# AIO-RF-v2-Sheet2.net
KiCad netlist of a schematic drawn in Altium Designer
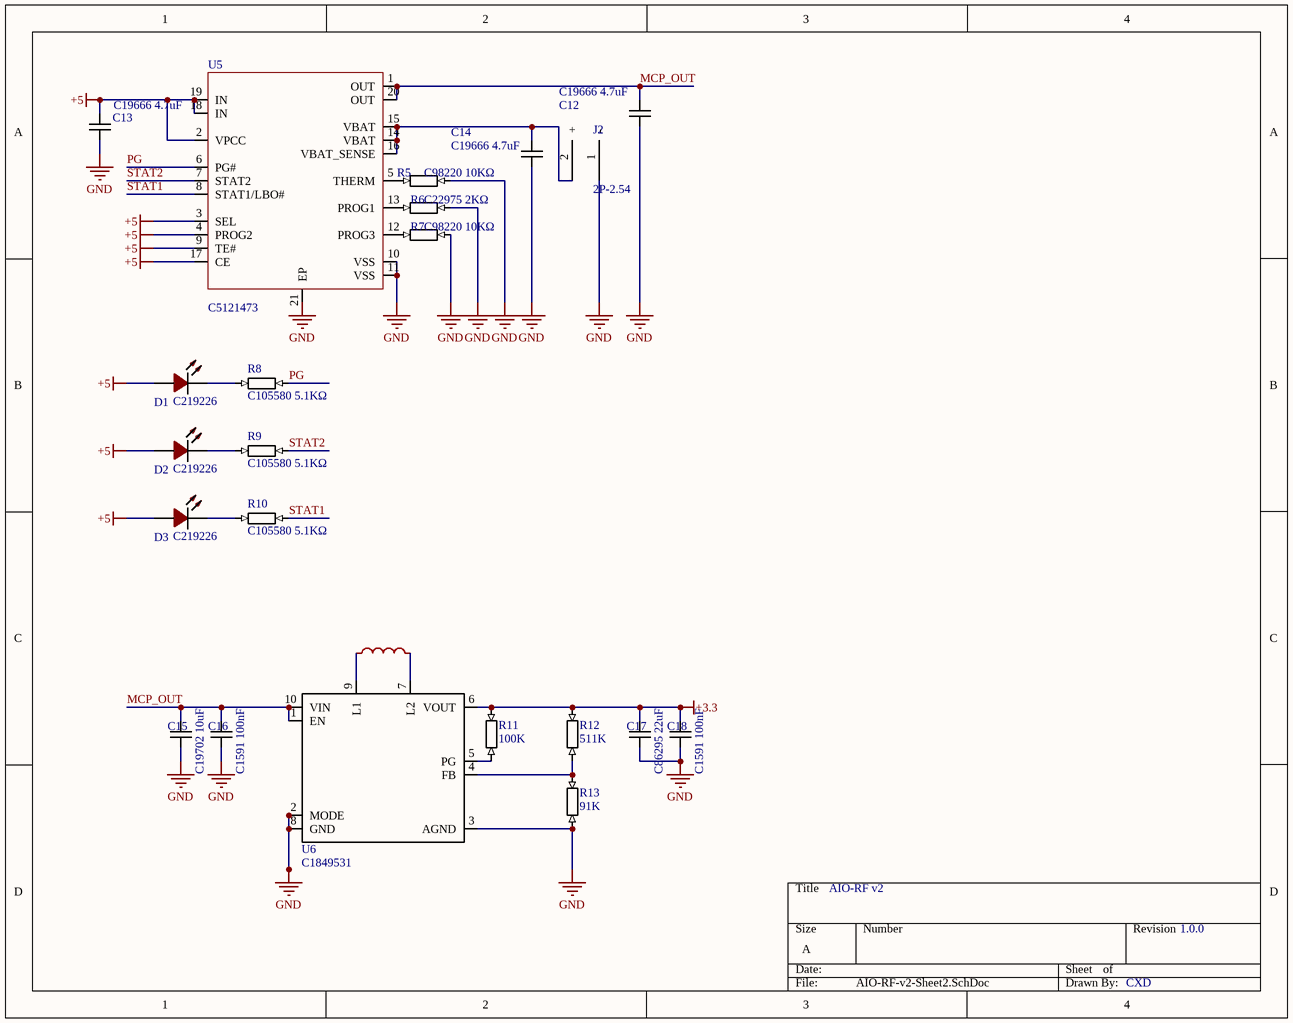
[diagram p0: AIO-RF-v2-Sheet2.SchDoc]

(export (version "E")
  (design (tool "Eeschema 10.0.6"))
  (components
    (comp (ref "C12")
      (value "C19666 4.7uF")
      (footprint "C19666")
      (description "4.7uF (475) ±10% 16V")
      (fields
        (field (name "LCSC PART NUMBER") "C19666")
        (field (name "MANUFACTURER") "SAMSUNG(三星)")
        (field (name "IMPORTED BY") "JLCAltiumImporter 0.3.1")
      )
      (libsource (lib "Schlib1") (part "C19666"))
    )
    (comp (ref "C13")
      (value "C19666 4.7uF")
      (footprint "C19666")
      (description "4.7uF (475) ±10% 16V")
      (fields
        (field (name "LCSC PART NUMBER") "C19666")
        (field (name "MANUFACTURER") "SAMSUNG(三星)")
        (field (name "IMPORTED BY") "JLCAltiumImporter 0.3.1")
      )
      (libsource (lib "Schlib1") (part "C19666"))
    )
    (comp (ref "C14")
      (value "C19666 4.7uF")
      (footprint "C19666")
      (description "4.7uF (475) ±10% 16V")
      (fields
        (field (name "LCSC PART NUMBER") "C19666")
        (field (name "MANUFACTURER") "SAMSUNG(三星)")
        (field (name "IMPORTED BY") "JLCAltiumImporter 0.3.1")
      )
      (libsource (lib "Schlib1") (part "C19666"))
    )
    (comp (ref "C15")
      (value "C19702 10uF")
      (footprint "C19702")
      (fields
        (field (name "LCSC PART NUMBER") "C19702")
        (field (name "MANUFACTURER") "SAMSUNG(三星)")
        (field (name "MANUFACTURER PART NUMBER") "CL10A106KP8NNNC")
        (field (name "IMPORTED BY") "JLCAltiumImporter 0.3.1")
      )
      (libsource (lib "Schlib1") (part "C19702"))
    )
    (comp (ref "C16")
      (value "C1591 100nF")
      (footprint "C1591")
      (description "100nF (104) ±10% 50V")
      (fields
        (field (name "LCSC PART NUMBER") "C1591")
        (field (name "MANUFACTURER") "SAMSUNG(三星)")
        (field (name "IMPORTED BY") "JLCAltiumImporter 0.3.1")
      )
      (libsource (lib "Schlib1") (part "C1591"))
    )
    (comp (ref "C17")
      (value "C86295 22uF")
      (footprint "C86295")
      (fields
        (field (name "LCSC PART NUMBER") "C86295")
        (field (name "MANUFACTURER") "SAMSUNG(三星)")
        (field (name "MANUFACTURER PART NUMBER") "CL10A226MP8NUNE")
        (field (name "IMPORTED BY") "JLCAltiumImporter 0.3.1")
      )
      (libsource (lib "Schlib1") (part "C86295"))
    )
    (comp (ref "C18")
      (value "C1591 100nF")
      (footprint "C1591")
      (description "100nF (104) ±10% 50V")
      (fields
        (field (name "LCSC PART NUMBER") "C1591")
        (field (name "MANUFACTURER") "SAMSUNG(三星)")
        (field (name "IMPORTED BY") "JLCAltiumImporter 0.3.1")
      )
      (libsource (lib "Schlib1") (part "C1591"))
    )
    (comp (ref "D1")
      (value "C219226")
      (footprint "C219226")
      (fields
        (field (name "MANUFACTURER") "HONGLITRONIC(鸿利光电)")
        (field (name "MANUFACTURER PART NUMBER") "HL-PST-1608H233W(9000-16000K)")
        (field (name "IMPORTED BY") "JLCAltiumImporter 0.3.2")
      )
      (libsource (lib "Schlib1") (part "C219226"))
    )
    (comp (ref "D2")
      (value "C219226")
      (footprint "C219226")
      (fields
        (field (name "MANUFACTURER") "HONGLITRONIC(鸿利光电)")
        (field (name "MANUFACTURER PART NUMBER") "HL-PST-1608H233W(9000-16000K)")
        (field (name "IMPORTED BY") "JLCAltiumImporter 0.3.2")
      )
      (libsource (lib "Schlib1") (part "C219226"))
    )
    (comp (ref "D3")
      (value "C219226")
      (footprint "C219226")
      (fields
        (field (name "MANUFACTURER") "HONGLITRONIC(鸿利光电)")
        (field (name "MANUFACTURER PART NUMBER") "HL-PST-1608H233W(9000-16000K)")
        (field (name "IMPORTED BY") "JLCAltiumImporter 0.3.2")
      )
      (libsource (lib "Schlib1") (part "C219226"))
    )
    (comp (ref "J2")
      (value "2P-2.54")
      (footprint "PcbLib1:2P-2.54")
      (libsource (lib "Schlib1") (part "2P-2.54"))
    )
    (comp (ref "L1")
      (value "hctc-201610-1r0-m")
      (footprint "PcbLib1:Inductor")
      (fields
        (field (name "MANUFACTURER") "YOUCHI(佑驰)")
        (field (name "MANUFACTURERPART") "HCTC-201610-1R0-M")
      )
      (libsource (lib "altium-import") (part "root_0_hctc-201610-1r0-m_"))
    )
    (comp (ref "R5")
      (value "C98220 10KΩ")
      (footprint "C98220")
      (fields
        (field (name "LCSC PART NUMBER") "C98220")
        (field (name "MANUFACTURER") "YAGEO(国巨)")
        (field (name "MANUFACTURER PART NUMBER") "RC0603FR-0710KL")
        (field (name "IMPORTED BY") "JLCAltiumImporter 0.3.1")
      )
      (libsource (lib "Schlib1") (part "C98220"))
    )
    (comp (ref "R6")
      (value "C22975 2KΩ")
      (footprint "C22975")
      (description "2KΩ (2001) ±1%")
      (fields
        (field (name "LCSC PART NUMBER") "C22975")
        (field (name "MANUFACTURER") "UNI-ROYAL(厚声)")
        (field (name "IMPORTED BY") "JLCAltiumImporter 0.3.1")
      )
      (libsource (lib "Schlib1") (part "C22975"))
    )
    (comp (ref "R7")
      (value "C98220 10KΩ")
      (footprint "C98220")
      (fields
        (field (name "LCSC PART NUMBER") "C98220")
        (field (name "MANUFACTURER") "YAGEO(国巨)")
        (field (name "MANUFACTURER PART NUMBER") "RC0603FR-0710KL")
        (field (name "IMPORTED BY") "JLCAltiumImporter 0.3.1")
      )
      (libsource (lib "Schlib1") (part "C98220"))
    )
    (comp (ref "R8")
      (value "C105580 5.1KΩ")
      (footprint "C105580")
      (fields
        (field (name "MANUFACTURER") "YAGEO(国巨)")
        (field (name "MANUFACTURER PART NUMBER") "RC0603FR-075K1L")
        (field (name "LCSC PART NUMBER") "C105580")
        (field (name "IMPORTED BY") "JLCAltiumImporter 0.3.1")
      )
      (libsource (lib "Schlib1") (part "C105580"))
    )
    (comp (ref "R9")
      (value "C105580 5.1KΩ")
      (footprint "C105580")
      (fields
        (field (name "MANUFACTURER") "YAGEO(国巨)")
        (field (name "MANUFACTURER PART NUMBER") "RC0603FR-075K1L")
        (field (name "LCSC PART NUMBER") "C105580")
        (field (name "IMPORTED BY") "JLCAltiumImporter 0.3.1")
      )
      (libsource (lib "Schlib1") (part "C105580"))
    )
    (comp (ref "R10")
      (value "C105580 5.1KΩ")
      (footprint "C105580")
      (fields
        (field (name "MANUFACTURER") "YAGEO(国巨)")
        (field (name "MANUFACTURER PART NUMBER") "RC0603FR-075K1L")
        (field (name "LCSC PART NUMBER") "C105580")
        (field (name "IMPORTED BY") "JLCAltiumImporter 0.3.1")
      )
      (libsource (lib "Schlib1") (part "C105580"))
    )
    (comp (ref "R11")
      (value "100K")
      (footprint "C22975")
      (description "2KΩ (2001) ±1%")
      (fields
        (field (name "LCSC PART NUMBER") "C22975")
        (field (name "MANUFACTURER") "UNI-ROYAL(厚声)")
        (field (name "IMPORTED BY") "JLCAltiumImporter 0.3.1")
      )
      (libsource (lib "Schlib1") (part "C22975"))
    )
    (comp (ref "R12")
      (value "511K")
      (footprint "C22975")
      (description "2KΩ (2001) ±1%")
      (fields
        (field (name "LCSC PART NUMBER") "C22975")
        (field (name "MANUFACTURER") "UNI-ROYAL(厚声)")
        (field (name "IMPORTED BY") "JLCAltiumImporter 0.3.1")
      )
      (libsource (lib "Schlib1") (part "C22975"))
    )
    (comp (ref "R13")
      (value "91K")
      (footprint "C22975")
      (description "2KΩ (2001) ±1%")
      (fields
        (field (name "LCSC PART NUMBER") "C22975")
        (field (name "MANUFACTURER") "UNI-ROYAL(厚声)")
        (field (name "IMPORTED BY") "JLCAltiumImporter 0.3.1")
      )
      (libsource (lib "Schlib1") (part "C22975"))
    )
    (comp (ref "U5")
      (value "C5121473")
      (footprint "C5121473")
      (fields
        (field (name "MANUFACTURER") "MICROCHIP(美国微芯)")
        (field (name "MANUFACTURER PART NUMBER") "MCP73871-2CCI/ML")
        (field (name "IMPORTED BY") "JLCAltiumImporter 0.3.1")
      )
      (libsource (lib "Schlib1") (part "C5121473"))
    )
    (comp (ref "U6")
      (value "C1849531")
      (footprint "C1849531")
      (fields
        (field (name "MANUFACTURER") "TI(德州仪器)")
        (field (name "MANUFACTURER PART NUMBER") "TPS63802DLAT")
        (field (name "IMPORTED BY") "JLCAltiumImporter 0.3.5")
      )
      (libsource (lib "Schlib1") (part "C1849531"))
    )
  )
  (nets
    (net (code "1") (name "+3.3") (class "Default")
      (node (ref "C17") (pin "2") (pinfunction "2_2") (pintype "passive"))
      (node (ref "C18") (pin "2") (pinfunction "2_2") (pintype "passive"))
      (node (ref "R11") (pin "2") (pinfunction "2_2") (pintype "input"))
      (node (ref "R12") (pin "2") (pinfunction "2_2") (pintype "input"))
      (node (ref "U6") (pin "6") (pinfunction "VOUT_6") (pintype "passive"))
    )
    (net (code "2") (name "+5") (class "Default")
      (node (ref "C13") (pin "2") (pinfunction "2_2") (pintype "passive"))
      (node (ref "D1") (pin "2") (pinfunction "A_2") (pintype "passive"))
      (node (ref "D2") (pin "2") (pinfunction "A_2") (pintype "passive"))
      (node (ref "D3") (pin "2") (pinfunction "A_2") (pintype "passive"))
      (node (ref "U5") (pin "17") (pinfunction "CE_17") (pintype "passive"))
      (node (ref "U5") (pin "18") (pinfunction "IN_18") (pintype "passive"))
      (node (ref "U5") (pin "19") (pinfunction "IN_19") (pintype "passive"))
      (node (ref "U5") (pin "2") (pinfunction "VPCC_2") (pintype "passive"))
      (node (ref "U5") (pin "3") (pinfunction "SEL_3") (pintype "passive"))
      (node (ref "U5") (pin "4") (pinfunction "PROG2_4") (pintype "passive"))
      (node (ref "U5") (pin "9") (pinfunction "TE#_9") (pintype "passive"))
    )
    (net (code "3") (name "/MCP_OUT") (class "Default")
      (node (ref "C12") (pin "2") (pinfunction "2_2") (pintype "passive"))
      (node (ref "C15") (pin "2") (pinfunction "2_2") (pintype "passive"))
      (node (ref "C16") (pin "2") (pinfunction "2_2") (pintype "passive"))
      (node (ref "U5") (pin "1") (pinfunction "OUT_1") (pintype "passive"))
      (node (ref "U5") (pin "20") (pinfunction "OUT_20") (pintype "passive"))
      (node (ref "U6") (pin "1") (pinfunction "EN_1") (pintype "passive"))
      (node (ref "U6") (pin "10") (pinfunction "VIN_10") (pintype "passive"))
    )
    (net (code "4") (name "/PG") (class "Default")
      (node (ref "R8") (pin "1") (pinfunction "1_1") (pintype "input"))
      (node (ref "U5") (pin "6") (pinfunction "PG#_6") (pintype "passive"))
    )
    (net (code "5") (name "/STAT1") (class "Default")
      (node (ref "R10") (pin "1") (pinfunction "1_1") (pintype "input"))
      (node (ref "U5") (pin "8") (pinfunction "STAT1/LBO#_8") (pintype "passive"))
    )
    (net (code "6") (name "/STAT2") (class "Default")
      (node (ref "R9") (pin "1") (pinfunction "1_1") (pintype "input"))
      (node (ref "U5") (pin "7") (pinfunction "STAT2_7") (pintype "passive"))
    )
    (net (code "7") (name "GND") (class "Default")
      (node (ref "C12") (pin "1") (pinfunction "1_1") (pintype "passive"))
      (node (ref "C13") (pin "1") (pinfunction "1_1") (pintype "passive"))
      (node (ref "C14") (pin "1") (pinfunction "1_1") (pintype "passive"))
      (node (ref "C15") (pin "1") (pinfunction "1_1") (pintype "passive"))
      (node (ref "C16") (pin "1") (pinfunction "1_1") (pintype "passive"))
      (node (ref "C17") (pin "1") (pinfunction "1_1") (pintype "passive"))
      (node (ref "C18") (pin "1") (pinfunction "1_1") (pintype "passive"))
      (node (ref "J2") (pin "1") (pinfunction "-_1") (pintype "passive"))
      (node (ref "R13") (pin "1") (pinfunction "1_1") (pintype "input"))
      (node (ref "R5") (pin "1") (pinfunction "1_1") (pintype "input"))
      (node (ref "R6") (pin "2") (pinfunction "2_2") (pintype "input"))
      (node (ref "R7") (pin "1") (pinfunction "1_1") (pintype "input"))
      (node (ref "U5") (pin "10") (pinfunction "VSS_10") (pintype "passive"))
      (node (ref "U5") (pin "11") (pinfunction "VSS_11") (pintype "passive"))
      (node (ref "U5") (pin "21") (pinfunction "EP_21") (pintype "passive"))
      (node (ref "U6") (pin "2") (pinfunction "MODE_2") (pintype "passive"))
      (node (ref "U6") (pin "3") (pinfunction "AGND_3") (pintype "passive"))
      (node (ref "U6") (pin "8") (pinfunction "GND_8") (pintype "passive"))
    )
    (net (code "8") (name "Net-(D1-C)") (class "Default")
      (node (ref "D1") (pin "1") (pinfunction "C_1") (pintype "passive"))
      (node (ref "R8") (pin "2") (pinfunction "2_2") (pintype "input"))
    )
    (net (code "9") (name "Net-(D2-C)") (class "Default")
      (node (ref "D2") (pin "1") (pinfunction "C_1") (pintype "passive"))
      (node (ref "R9") (pin "2") (pinfunction "2_2") (pintype "input"))
    )
    (net (code "10") (name "Net-(D3-C)") (class "Default")
      (node (ref "D3") (pin "1") (pinfunction "C_1") (pintype "passive"))
      (node (ref "R10") (pin "2") (pinfunction "2_2") (pintype "input"))
    )
    (net (code "11") (name "Net-(J2-+)") (class "Default")
      (node (ref "C14") (pin "2") (pinfunction "2_2") (pintype "passive"))
      (node (ref "J2") (pin "2") (pinfunction "+_2") (pintype "passive"))
      (node (ref "U5") (pin "14") (pinfunction "VBAT_14") (pintype "passive"))
      (node (ref "U5") (pin "15") (pinfunction "VBAT_15") (pintype "passive"))
      (node (ref "U5") (pin "16") (pinfunction "VBAT_SENSE_16") (pintype "passive"))
    )
    (net (code "12") (name "Net-(U5-PROG1)") (class "Default")
      (node (ref "R6") (pin "1") (pinfunction "1_1") (pintype "input"))
      (node (ref "U5") (pin "13") (pinfunction "PROG1_13") (pintype "passive"))
    )
    (net (code "13") (name "Net-(U5-PROG3)") (class "Default")
      (node (ref "R7") (pin "2") (pinfunction "2_2") (pintype "input"))
      (node (ref "U5") (pin "12") (pinfunction "PROG3_12") (pintype "passive"))
    )
    (net (code "14") (name "Net-(U5-THERM)") (class "Default")
      (node (ref "R5") (pin "2") (pinfunction "2_2") (pintype "input"))
      (node (ref "U5") (pin "5") (pinfunction "THERM_5") (pintype "passive"))
    )
    (net (code "15") (name "Net-(U6-FB)") (class "Default")
      (node (ref "R12") (pin "1") (pinfunction "1_1") (pintype "input"))
      (node (ref "R13") (pin "2") (pinfunction "2_2") (pintype "input"))
      (node (ref "U6") (pin "4") (pinfunction "FB_4") (pintype "passive"))
    )
    (net (code "16") (name "Net-(U6-L1)") (class "Default")
      (node (ref "L1") (pin "1") (pinfunction "1_1") (pintype "passive"))
      (node (ref "U6") (pin "9") (pinfunction "L1_9") (pintype "passive"))
    )
    (net (code "17") (name "Net-(U6-L2)") (class "Default")
      (node (ref "L1") (pin "2") (pinfunction "2_2") (pintype "passive"))
      (node (ref "U6") (pin "7") (pinfunction "L2_7") (pintype "passive"))
    )
    (net (code "18") (name "Net-(U6-PG)") (class "Default")
      (node (ref "R11") (pin "1") (pinfunction "1_1") (pintype "input"))
      (node (ref "U6") (pin "5") (pinfunction "PG_5") (pintype "passive"))
    )
  )
)
